# Supply.net
KiCad netlist of a schematic drawn in Altium Designer
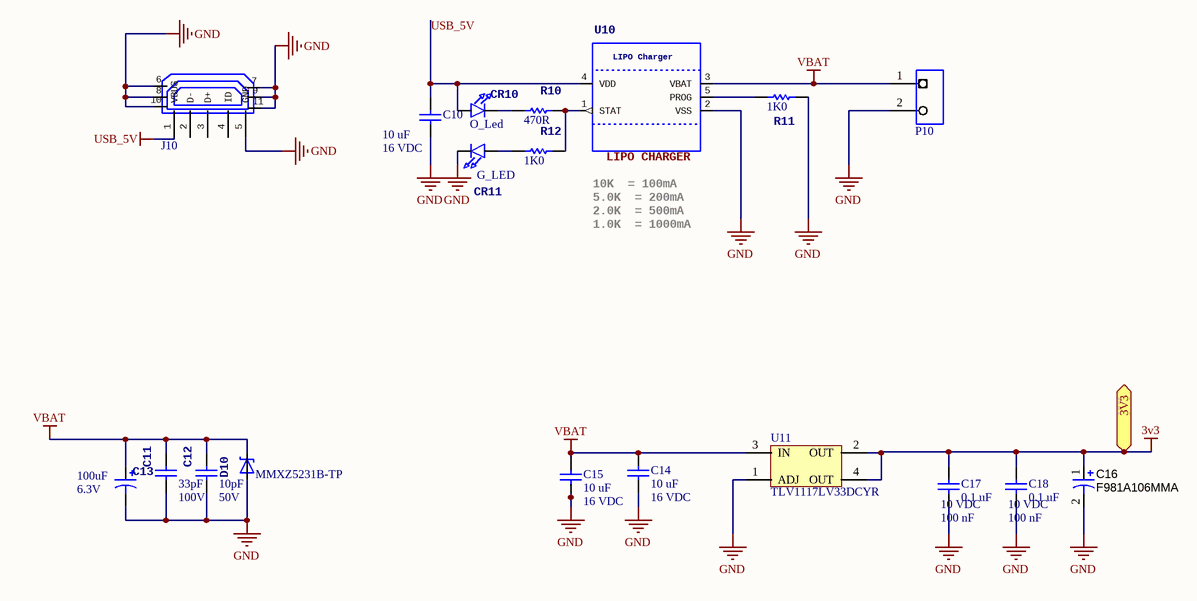
[diagram p0: Supply.SchDoc]

(export (version "E")
  (design (tool "Eeschema 10.0.6"))
  (components
    (comp (ref "C10")
      (value "EMK107BBJ106MA-T")
      (footprint "C0603")
      (description "Cap_Cer")
      (fields
        (field (name "MANUFACTURER") "Taiyo Yuden")
        (field (name "TOLERANCE") "20 %")
        (field (name "CAPACITANCE") "10 uF")
        (field (name "VOLTAGE RATING DC") "16 VDC")
      )
      (libsource (lib "PULV3") (part "10 uF, 16 V"))
    )
    (comp (ref "C11")
      (value "08051A330JAT2A")
      (footprint "0805-C")
      (description "Cap_Cer")
      (fields
        (field (name "MANUFACTURER") "AVX")
        (field (name "CAPACITANCE") "33pF")
        (field (name "VOLTAGE RATING") "100V")
      )
      (libsource (lib "PULV3") (part "33pF, 100V"))
    )
    (comp (ref "C12")
      (value "04025A100JAT2A")
      (footprint "0805-C")
      (description "Cap_Cer")
      (fields
        (field (name "MANUFACTURER") "AVX")
        (field (name "CAPACITANCE") "10pF")
        (field (name "VOLTAGE RATING") "50V")
      )
      (libsource (lib "PULV3") (part "10pF, 50V"))
    )
    (comp (ref "C13")
      (value "C3225X6S0J107M250AC")
      (footprint "C1210")
      (description "Cap_Pol")
      (fields
        (field (name "MANUFACTURER") "TDK")
        (field (name "CAPACITANCE") "100uF")
        (field (name "VOLTAGE RATING") "6.3V")
      )
      (libsource (lib "PULV3") (part "100uF, 6.3V"))
    )
    (comp (ref "C14")
      (value "EMK107BBJ106MA-T")
      (footprint "C0603")
      (description "Cap_Cer")
      (fields
        (field (name "MANUFACTURER") "Taiyo Yuden")
        (field (name "TOLERANCE") "20 %")
        (field (name "CAPACITANCE") "10 uF")
        (field (name "VOLTAGE RATING DC") "16 VDC")
      )
      (libsource (lib "PULV3") (part "10 uF, 16 V"))
    )
    (comp (ref "C15")
      (value "EMK107BBJ106MA-T")
      (footprint "C0603")
      (description "Cap_Cer")
      (fields
        (field (name "MANUFACTURER") "Taiyo Yuden")
        (field (name "TOLERANCE") "20 %")
        (field (name "CAPACITANCE") "10 uF")
        (field (name "VOLTAGE RATING DC") "16 VDC")
      )
      (libsource (lib "PULV3") (part "10 uF, 16 V"))
    )
    (comp (ref "C16")
      (value "F981A106MMA")
      (footprint "C0603_P")
      (description "CAP_TAN")
      (libsource (lib "PULV3") (part "10UF, 10V, C_TAN"))
    )
    (comp (ref "C17")
      (value "100 nF, 10 V")
      (footprint "C0402")
      (description "Cap_Cer")
      (fields
        (field (name "MANUFACTURER") "Murata Electronics")
        (field (name "MANUFACTURER PART NUMBER") "GRM155R71A104KA01D")
        (field (name "CAPACITANCE") "0.1 uF")
        (field (name "VOLTAGE RATING DC") "10 VDC")
        (field (name "CAPACITANCE - NF") "100 nF")
      )
      (libsource (lib "PULV3") (part "100 nF, 10 V"))
    )
    (comp (ref "C18")
      (value "100 nF, 10 V")
      (footprint "C0402")
      (description "Cap_Cer")
      (fields
        (field (name "MANUFACTURER") "Murata Electronics")
        (field (name "MANUFACTURER PART NUMBER") "GRM155R71A104KA01D")
        (field (name "CAPACITANCE") "0.1 uF")
        (field (name "VOLTAGE RATING DC") "10 VDC")
        (field (name "CAPACITANCE - NF") "100 nF")
      )
      (libsource (lib "PULV3") (part "100 nF, 10 V"))
    )
    (comp (ref "CR10")
      (value "Led_Orange_0402")
      (footprint "0402-LED_RED")
      (description "Led_Orange")
      (fields
        (field (name "MANUFACTURER") "ROHM Semiconductor")
        (field (name "MANUFACTURER PART NUMBER") "SML-P12DTT86R")
        (field (name "PRODUCT") "O_Led")
      )
      (libsource (lib "PULV5") (part "Led_Orange_0402"))
    )
    (comp (ref "CR11")
      (value "SML-P11MTT86R")
      (footprint "0402-LED_GRE")
      (description "Led_Green")
      (fields (field (name "MANUFACTURER") "ROHM Semiconductor") (field (name "PRODUCT") "G_LED"))
      (libsource (lib "PULV5") (part "Led_Green_0402"))
    )
    (comp (ref "D10")
      (value "MMSZ5231BT1G")
      (footprint "SOD-123")
      (description "Diode_Zener")
      (fields
        (field (name "MANUFACTURER") "MICRO COMMERCIAL COMPONENTS")
        (field (name "MANUFACTURER PART NUMBER") "MMXZ5231B-TP")
      )
      (libsource (lib "PULV3") (part "Diode_Zener"))
    )
    (comp (ref "J10")
      (value "1981568-1")
      (footprint "TYCO_19815681N")
      (description "Micro USB")
      (fields (field (name "MANUFACTURER") "AMP - TE CONNECTIVITY"))
      (libsource (lib "PULV3") (part "USB"))
    )
    (comp (ref "P10")
      (value "header")
      (footprint "HDR1X2")
      (description "Bateria")
      (fields (field (name "MANUFACTURER PART NUMBER") "No aplica"))
      (libsource (lib "PULV3") (part "header"))
    )
    (comp (ref "R10")
      (value "CRCW0805470RJNEA")
      (footprint "0805-R")
      (description "Resistor")
      (fields (field (name "MANUFACTURER") "VISHAY") (field (name "RESISTANCE") "470R"))
      (libsource (lib "PULV3") (part "470R0, 125mW"))
    )
    (comp (ref "R11")
      (value "CRCW08051K00JNEB")
      (footprint "0805-R")
      (description "Resistor")
      (fields (field (name "MANUFACTURER") "VISHAY") (field (name "RESISTANCE") "1K0"))
      (libsource (lib "PULV3") (part "1K0, 125mW"))
    )
    (comp (ref "R12")
      (value "CRCW08051K00JNEB")
      (footprint "0805-R")
      (description "Resistor")
      (fields (field (name "MANUFACTURER") "VISHAY") (field (name "RESISTANCE") "1K0"))
      (libsource (lib "PULV3") (part "1K0, 125mW"))
    )
    (comp (ref "U10")
      (value "MCP73831T-2ACI/OT")
      (footprint "SOT23-5")
      (description "Charger")
      (fields (field (name "MANUFACTURER") "MICROCHIP") (field (name "LIPO CHARGER") "LIPO Charger"))
      (libsource (lib "PULV3") (part "MCP73831/2"))
    )
    (comp (ref "U11")
      (value "TLV1117LV33DCYR")
      (footprint "SOT230P700X180-4AN")
      (description "Regulador3V3")
      (fields
        (field (name "MANUFACTURER") "TEXAS INSTRUMENTS")
        (field (name "MANUFACTURER PART NUMBER") "TLV1117LV33DCYR")
      )
      (libsource (lib "PULV3") (part "IC,LDO,3V3,1A,TLV1117LV"))
    )
  )
  (nets
    (net (code "1") (name "3v3") (class "Default")
      (node (ref "C16") (pin "1") (pinfunction "+_1") (pintype "passive"))
      (node (ref "C17") (pin "1") (pinfunction "1_1") (pintype "passive"))
      (node (ref "C18") (pin "1") (pinfunction "1_1") (pintype "passive"))
      (node (ref "U11") (pin "2") (pinfunction "OUT_2") (pintype "passive"))
      (node (ref "U11") (pin "4") (pinfunction "OUT_4") (pintype "passive"))
    )
    (net (code "2") (name "GND") (class "Default")
      (node (ref "C10") (pin "2") (pinfunction "2_2") (pintype "passive"))
      (node (ref "C11") (pin "2") (pinfunction "2_2") (pintype "passive"))
      (node (ref "C12") (pin "2") (pinfunction "2_2") (pintype "passive"))
      (node (ref "C13") (pin "2") (pinfunction "-_2") (pintype "passive"))
      (node (ref "C14") (pin "2") (pinfunction "2_2") (pintype "passive"))
      (node (ref "C15") (pin "2") (pinfunction "2_2") (pintype "passive"))
      (node (ref "C16") (pin "2") (pinfunction "-_2") (pintype "passive"))
      (node (ref "C17") (pin "2") (pinfunction "2_2") (pintype "passive"))
      (node (ref "C18") (pin "2") (pinfunction "2_2") (pintype "passive"))
      (node (ref "CR11") (pin "K") (pinfunction "K_K") (pintype "passive"))
      (node (ref "D10") (pin "A") (pinfunction "A_A") (pintype "passive"))
      (node (ref "J10") (pin "10") (pinfunction "10_10") (pintype "passive"))
      (node (ref "J10") (pin "11") (pinfunction "11_11") (pintype "passive"))
      (node (ref "J10") (pin "5") (pinfunction "GND_5") (pintype "passive"))
      (node (ref "J10") (pin "6") (pinfunction "6_6") (pintype "passive"))
      (node (ref "J10") (pin "7") (pinfunction "7_7") (pintype "passive"))
      (node (ref "J10") (pin "8") (pinfunction "8_8") (pintype "passive"))
      (node (ref "J10") (pin "9") (pinfunction "9_9") (pintype "passive"))
      (node (ref "P10") (pin "2") (pintype "passive"))
      (node (ref "R11") (pin "2") (pinfunction "2_2") (pintype "passive"))
      (node (ref "U10") (pin "2") (pinfunction "VSS_2") (pintype "passive"))
      (node (ref "U11") (pin "1") (pinfunction "ADJ_1") (pintype "passive"))
    )
    (net (code "3") (name "Net-(CR10-PadK)") (class "Default")
      (node (ref "CR10") (pin "K") (pinfunction "K_K") (pintype "passive"))
      (node (ref "R10") (pin "1") (pinfunction "1_1") (pintype "passive"))
    )
    (net (code "4") (name "Net-(CR11-PadA)") (class "Default")
      (node (ref "CR11") (pin "A") (pinfunction "A_A") (pintype "passive"))
      (node (ref "R12") (pin "1") (pinfunction "1_1") (pintype "passive"))
    )
    (net (code "5") (name "Net-(U10-PROG)") (class "Default")
      (node (ref "R11") (pin "1") (pinfunction "1_1") (pintype "passive"))
      (node (ref "U10") (pin "5") (pinfunction "PROG_5") (pintype "passive"))
    )
    (net (code "6") (name "Net-(U10-STAT)") (class "Default")
      (node (ref "R10") (pin "2") (pinfunction "2_2") (pintype "passive"))
      (node (ref "R12") (pin "2") (pinfunction "2_2") (pintype "passive"))
      (node (ref "U10") (pin "1") (pinfunction "STAT_1") (pintype "output"))
    )
    (net (code "7") (name "USB_5V") (class "Default")
      (node (ref "C10") (pin "1") (pinfunction "1_1") (pintype "passive"))
      (node (ref "CR10") (pin "A") (pinfunction "A_A") (pintype "passive"))
      (node (ref "J10") (pin "1") (pinfunction "VBUS_1") (pintype "passive"))
      (node (ref "U10") (pin "4") (pinfunction "VDD_4") (pintype "power_in"))
    )
    (net (code "8") (name "VBAT") (class "Default")
      (node (ref "C11") (pin "1") (pinfunction "1_1") (pintype "passive"))
      (node (ref "C12") (pin "1") (pinfunction "1_1") (pintype "passive"))
      (node (ref "C13") (pin "1") (pinfunction "+_1") (pintype "passive"))
      (node (ref "C14") (pin "1") (pinfunction "1_1") (pintype "passive"))
      (node (ref "C15") (pin "1") (pinfunction "1_1") (pintype "passive"))
      (node (ref "D10") (pin "C") (pinfunction "C_C") (pintype "passive"))
      (node (ref "P10") (pin "1") (pintype "passive"))
      (node (ref "U10") (pin "3") (pinfunction "VBAT_3") (pintype "power_in"))
      (node (ref "U11") (pin "3") (pinfunction "IN_3") (pintype "passive"))
    )
    (net (code "9") (name "unconnected-(J10-D+-Pad3)") (class "Default")
      (node (ref "J10") (pin "3") (pinfunction "D+_3") (pintype "passive"))
    )
    (net (code "10") (name "unconnected-(J10-D--Pad2)") (class "Default")
      (node (ref "J10") (pin "2") (pinfunction "D-_2") (pintype "passive"))
    )
    (net (code "11") (name "unconnected-(J10-ID-Pad4)") (class "Default")
      (node (ref "J10") (pin "4") (pinfunction "ID_4") (pintype "passive"))
    )
  )
)
